# voltage_switch.net
KiCad netlist of a schematic drawn in EAGLE
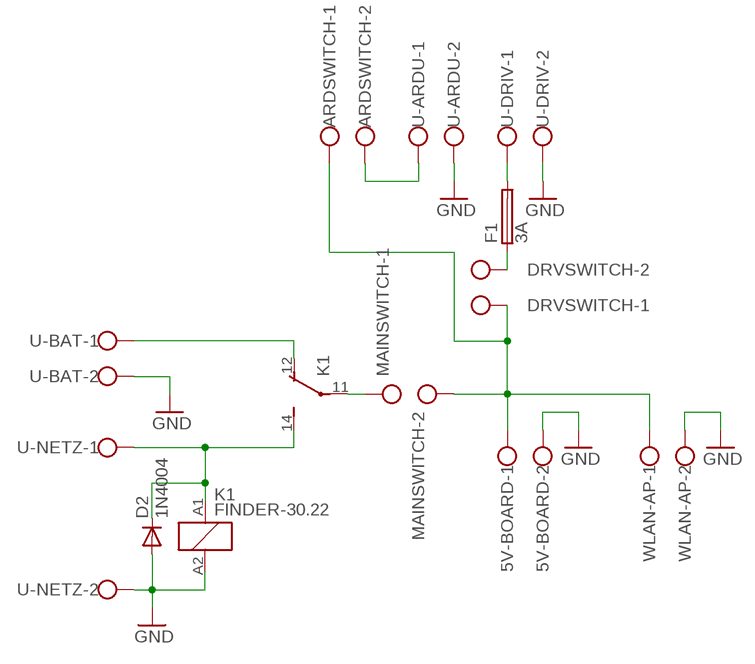
[diagram p0: schematic, sheet 1]

(export (version "E")
  (design (tool "Eeschema 10.0.6"))
  (components
    (comp (ref "5V-BOARD")
      (value "W237-102")
      (footprint "eagle-import:W237-102")
      (fields (field (name "MPN") "237-102"))
      (libsource (lib "eagle-import") (part "W237-102"))
    )
    (comp (ref "ARDSWITCH")
      (value "W237-102")
      (footprint "eagle-import:W237-102")
      (fields (field (name "MPN") "237-102"))
      (libsource (lib "eagle-import") (part "W237-102"))
    )
    (comp (ref "D2")
      (value "1N4004")
      (footprint "eagle-import:DO41-10")
      (libsource (lib "eagle-import") (part "1N4004"))
    )
    (comp (ref "DRVSWITCH")
      (value "W237-102")
      (footprint "eagle-import:W237-102")
      (fields (field (name "MPN") "237-102"))
      (libsource (lib "eagle-import") (part "W237-102"))
    )
    (comp (ref "F1")
      (value "3A")
      (footprint "eagle-import:GSH15")
      (fields (field (name "MPN") "64900001039"))
      (libsource (lib "eagle-import") (part "GSH15"))
    )
    (comp (ref "K1")
      (value "FINDER-30.22")
      (footprint "eagle-import:FINDER-30.22")
      (libsource (lib "eagle-import") (part "FINDER-30.22"))
    )
    (comp (ref "MAINSWITCH")
      (value "W237-102")
      (footprint "eagle-import:W237-102")
      (fields (field (name "MPN") "237-102"))
      (libsource (lib "eagle-import") (part "W237-102"))
    )
    (comp (ref "U-ARDU")
      (value "W237-102")
      (footprint "eagle-import:W237-102")
      (fields (field (name "MPN") "237-102"))
      (libsource (lib "eagle-import") (part "W237-102"))
    )
    (comp (ref "U-BAT")
      (value "W237-102")
      (footprint "eagle-import:W237-102")
      (fields (field (name "MPN") "237-102"))
      (libsource (lib "eagle-import") (part "W237-102"))
    )
    (comp (ref "U-DRIV")
      (value "W237-102")
      (footprint "eagle-import:W237-102")
      (fields (field (name "MPN") "237-102"))
      (libsource (lib "eagle-import") (part "W237-102"))
    )
    (comp (ref "U-NETZ")
      (value "W237-102")
      (footprint "eagle-import:W237-102")
      (fields (field (name "MPN") "237-102"))
      (libsource (lib "eagle-import") (part "W237-102"))
    )
    (comp (ref "WLAN-AP")
      (value "W237-102")
      (footprint "eagle-import:W237-102")
      (fields (field (name "MPN") "237-102"))
      (libsource (lib "eagle-import") (part "W237-102"))
    )
  )
  (nets
    (net (code "1") (name "GND") (class "Default")
      (node (ref "5V-BOARD") (pin "2") (pinfunction "KL_2") (pintype "passive"))
      (node (ref "D2") (pin "A") (pinfunction "A_A") (pintype "passive"))
      (node (ref "K1") (pin "A2") (pinfunction "2_A2") (pintype "passive"))
      (node (ref "U-ARDU") (pin "2") (pinfunction "KL_2") (pintype "passive"))
      (node (ref "U-BAT") (pin "2") (pinfunction "KL_2") (pintype "passive"))
      (node (ref "U-DRIV") (pin "2") (pinfunction "KL_2") (pintype "passive"))
      (node (ref "U-NETZ") (pin "2") (pinfunction "KL_2") (pintype "passive"))
      (node (ref "WLAN-AP") (pin "2") (pinfunction "KL_2") (pintype "passive"))
    )
    (net (code "2") (name "Net-(5V-BOARDA-KL)") (class "Default")
      (node (ref "5V-BOARD") (pin "1") (pinfunction "KL_1") (pintype "passive"))
      (node (ref "ARDSWITCH") (pin "1") (pinfunction "KL_1") (pintype "passive"))
      (node (ref "DRVSWITCH") (pin "1") (pinfunction "KL_1") (pintype "passive"))
      (node (ref "MAINSWITCH") (pin "2") (pinfunction "KL_2") (pintype "passive"))
      (node (ref "WLAN-AP") (pin "1") (pinfunction "KL_1") (pintype "passive"))
    )
    (net (code "3") (name "Net-(ARDSWITCHB-KL)") (class "Default")
      (node (ref "ARDSWITCH") (pin "2") (pinfunction "KL_2") (pintype "passive"))
      (node (ref "U-ARDU") (pin "1") (pinfunction "KL_1") (pintype "passive"))
    )
    (net (code "4") (name "Net-(DRVSWITCHB-KL)") (class "Default")
      (node (ref "DRVSWITCH") (pin "2") (pinfunction "KL_2") (pintype "passive"))
      (node (ref "F1") (pin "1") (pinfunction "1_1") (pintype "passive"))
    )
    (net (code "5") (name "Net-(K1A-O)") (class "Default")
      (node (ref "K1") (pin "12") (pinfunction "O_12") (pintype "passive"))
      (node (ref "U-BAT") (pin "1") (pinfunction "KL_1") (pintype "passive"))
    )
    (net (code "6") (name "Net-(K1A-P)") (class "Default")
      (node (ref "K1") (pin "11") (pinfunction "P_11") (pintype "passive"))
      (node (ref "MAINSWITCH") (pin "1") (pinfunction "KL_1") (pintype "passive"))
    )
    (net (code "7") (name "Net-(K1A-S)") (class "Default")
      (node (ref "D2") (pin "C") (pinfunction "C_C") (pintype "passive"))
      (node (ref "K1") (pin "14") (pinfunction "S_14") (pintype "passive"))
      (node (ref "K1") (pin "A1") (pinfunction "1_A1") (pintype "passive"))
      (node (ref "U-NETZ") (pin "1") (pinfunction "KL_1") (pintype "passive"))
    )
    (net (code "8") (name "Net-(U-DRIVA-KL)") (class "Default")
      (node (ref "F1") (pin "2") (pinfunction "2_2") (pintype "passive"))
      (node (ref "U-DRIV") (pin "1") (pinfunction "KL_1") (pintype "passive"))
    )
  )
)
